# Display.net
KiCad netlist of a schematic drawn in EAGLE
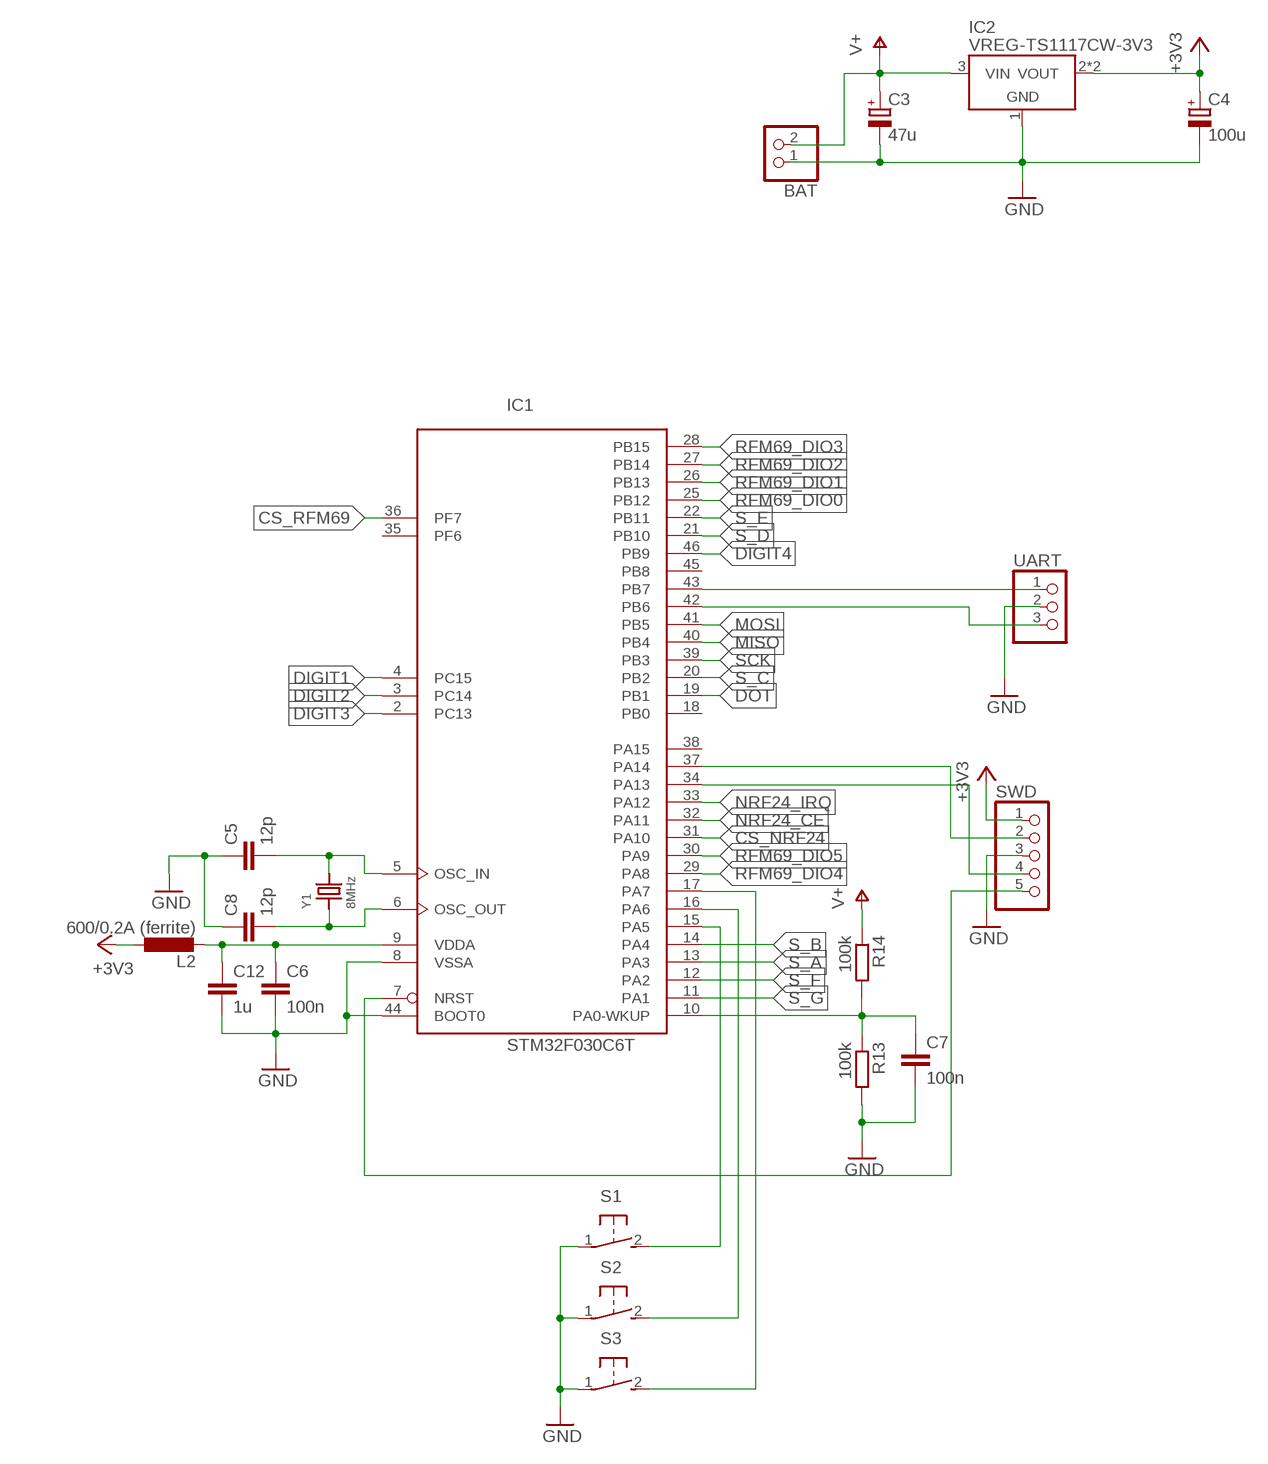
[diagram p0: schematic, sheet 1, part 1 of 2]
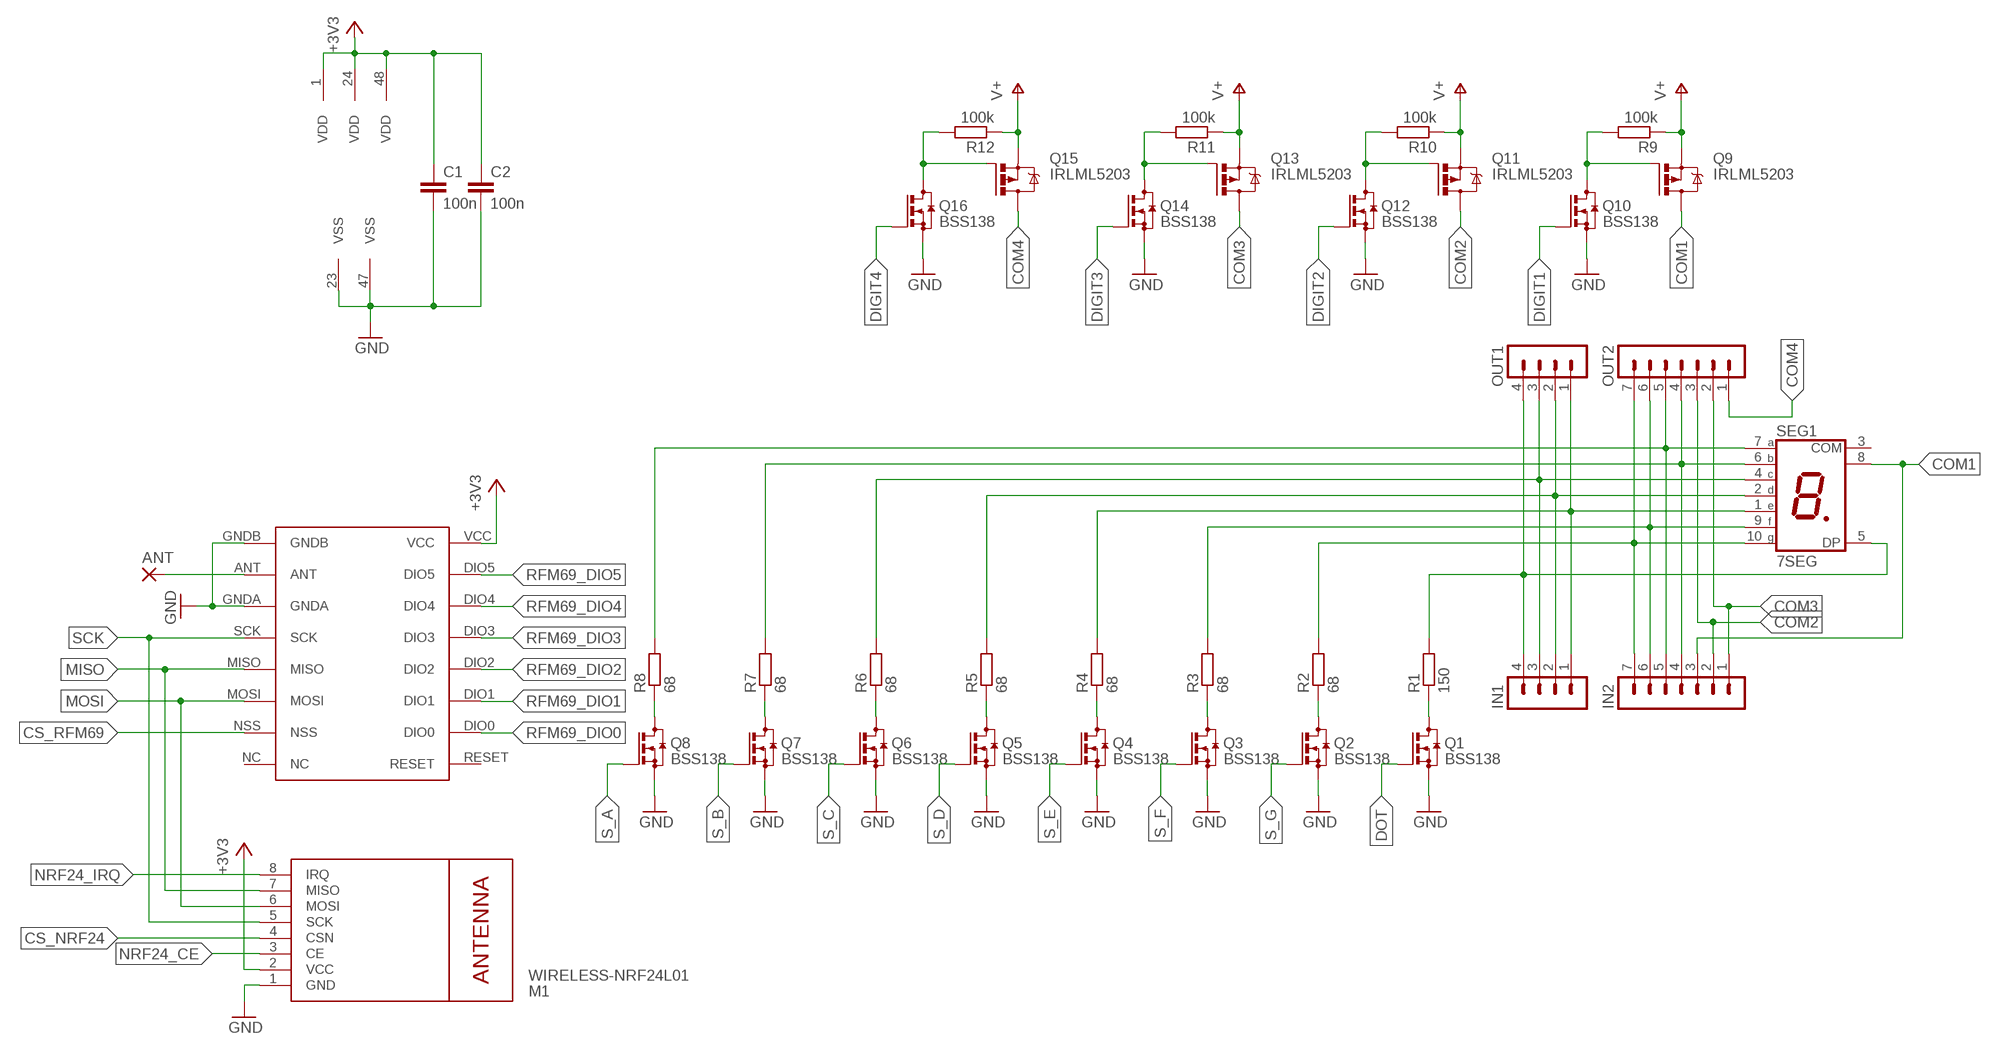
[diagram p1: schematic, sheet 1, part 2 of 2]

(export (version "E")
  (design (tool "Eeschema 10.0.6"))
  (components
    (comp (ref "ANT")
      (value "1,6/0,8")
      (footprint "eagle-import:1,6_0,8")
      (libsource (lib "eagle-import") (part "1,6/0,8"))
    )
    (comp (ref "BAT")
      (value "PINHD-1X2/90")
      (footprint "eagle-import:1X02_90")
      (libsource (lib "eagle-import") (part "PINHD-1X2/90"))
    )
    (comp (ref "C1")
      (value "100n")
      (footprint "eagle-import:C0603K")
      (libsource (lib "eagle-import") (part "C-EUC0603K"))
    )
    (comp (ref "C2")
      (value "100n")
      (footprint "eagle-import:C0603K")
      (libsource (lib "eagle-import") (part "C-EUC0603K"))
    )
    (comp (ref "C3")
      (value "47u")
      (footprint "eagle-import:E2,5-6")
      (libsource (lib "eagle-import") (part "CPOL-EUE2.5-6"))
    )
    (comp (ref "C4")
      (value "100u")
      (footprint "eagle-import:E2,5-6")
      (libsource (lib "eagle-import") (part "CPOL-EUE2.5-6"))
    )
    (comp (ref "C5")
      (value "12p")
      (footprint "eagle-import:C0603")
      (libsource (lib "eagle-import") (part "C-EUC0603"))
    )
    (comp (ref "C6")
      (value "100n")
      (footprint "eagle-import:C0603")
      (libsource (lib "eagle-import") (part "C-EUC0603"))
    )
    (comp (ref "C7")
      (value "100n")
      (footprint "eagle-import:C0603")
      (libsource (lib "eagle-import") (part "C-EUC0603"))
    )
    (comp (ref "C8")
      (value "12p")
      (footprint "eagle-import:C0603")
      (libsource (lib "eagle-import") (part "C-EUC0603"))
    )
    (comp (ref "C12")
      (value "1u")
      (footprint "eagle-import:C0603")
      (libsource (lib "eagle-import") (part "C-EUC0603"))
    )
    (comp (ref "IC1")
      (value "STM32F030C6T")
      (footprint "eagle-import:LQFP48")
      (libsource (lib "eagle-import") (part "STM32F030CT6"))
    )
    (comp (ref "IC2")
      (value "VREG-TS1117CW-3V3")
      (footprint "eagle-import:SOT223")
      (libsource (lib "eagle-import") (part "VREG-TS1117CW-3V3"))
    )
    (comp (ref "IN1")
      (value "MA04-1")
      (footprint "eagle-import:MA04-1")
      (libsource (lib "eagle-import") (part "MA04-1"))
    )
    (comp (ref "IN2")
      (value "MA07-1")
      (footprint "eagle-import:MA07-1")
      (libsource (lib "eagle-import") (part "MA07-1"))
    )
    (comp (ref "L2")
      (value "600/0.2A (ferrite)")
      (footprint "eagle-import:L2012C")
      (libsource (lib "eagle-import") (part "L-EUL2012C"))
    )
    (comp (ref "M1")
      (value "WIRELESS-NRF24L01")
      (footprint "eagle-import:WIRELESS-NRF24L01")
      (libsource (lib "eagle-import") (part "WIRELESS-NRF24L01"))
    )
    (comp (ref "OUT1")
      (value "MA04-1")
      (footprint "eagle-import:MA04-1")
      (libsource (lib "eagle-import") (part "MA04-1"))
    )
    (comp (ref "OUT2")
      (value "MA07-1")
      (footprint "eagle-import:MA07-1")
      (libsource (lib "eagle-import") (part "MA07-1"))
    )
    (comp (ref "Q1")
      (value "BSS138")
      (footprint "eagle-import:SOT23")
      (libsource (lib "eagle-import") (part "BSS123"))
    )
    (comp (ref "Q2")
      (value "BSS138")
      (footprint "eagle-import:SOT23")
      (libsource (lib "eagle-import") (part "BSS123"))
    )
    (comp (ref "Q3")
      (value "BSS138")
      (footprint "eagle-import:SOT23")
      (libsource (lib "eagle-import") (part "BSS123"))
    )
    (comp (ref "Q4")
      (value "BSS138")
      (footprint "eagle-import:SOT23")
      (libsource (lib "eagle-import") (part "BSS123"))
    )
    (comp (ref "Q5")
      (value "BSS138")
      (footprint "eagle-import:SOT23")
      (libsource (lib "eagle-import") (part "BSS123"))
    )
    (comp (ref "Q6")
      (value "BSS138")
      (footprint "eagle-import:SOT23")
      (libsource (lib "eagle-import") (part "BSS123"))
    )
    (comp (ref "Q7")
      (value "BSS138")
      (footprint "eagle-import:SOT23")
      (libsource (lib "eagle-import") (part "BSS123"))
    )
    (comp (ref "Q8")
      (value "BSS138")
      (footprint "eagle-import:SOT23")
      (libsource (lib "eagle-import") (part "BSS123"))
    )
    (comp (ref "Q9")
      (value "IRLML5203")
      (footprint "eagle-import:MICRO3")
      (libsource (lib "eagle-import") (part "IRLML5203"))
    )
    (comp (ref "Q10")
      (value "BSS138")
      (footprint "eagle-import:SOT23")
      (libsource (lib "eagle-import") (part "BSS123"))
    )
    (comp (ref "Q11")
      (value "IRLML5203")
      (footprint "eagle-import:MICRO3")
      (libsource (lib "eagle-import") (part "IRLML5203"))
    )
    (comp (ref "Q12")
      (value "BSS138")
      (footprint "eagle-import:SOT23")
      (libsource (lib "eagle-import") (part "BSS123"))
    )
    (comp (ref "Q13")
      (value "IRLML5203")
      (footprint "eagle-import:MICRO3")
      (libsource (lib "eagle-import") (part "IRLML5203"))
    )
    (comp (ref "Q14")
      (value "BSS138")
      (footprint "eagle-import:SOT23")
      (libsource (lib "eagle-import") (part "BSS123"))
    )
    (comp (ref "Q15")
      (value "IRLML5203")
      (footprint "eagle-import:MICRO3")
      (libsource (lib "eagle-import") (part "IRLML5203"))
    )
    (comp (ref "Q16")
      (value "BSS138")
      (footprint "eagle-import:SOT23")
      (libsource (lib "eagle-import") (part "BSS123"))
    )
    (comp (ref "R1")
      (value "150")
      (footprint "eagle-import:R1206")
      (libsource (lib "eagle-import") (part "R-EU_R1206"))
    )
    (comp (ref "R2")
      (value "68")
      (footprint "eagle-import:R1206")
      (libsource (lib "eagle-import") (part "R-EU_R1206"))
    )
    (comp (ref "R3")
      (value "68")
      (footprint "eagle-import:R1206")
      (libsource (lib "eagle-import") (part "R-EU_R1206"))
    )
    (comp (ref "R4")
      (value "68")
      (footprint "eagle-import:R1206")
      (libsource (lib "eagle-import") (part "R-EU_R1206"))
    )
    (comp (ref "R5")
      (value "68")
      (footprint "eagle-import:R1206")
      (libsource (lib "eagle-import") (part "R-EU_R1206"))
    )
    (comp (ref "R6")
      (value "68")
      (footprint "eagle-import:R1206")
      (libsource (lib "eagle-import") (part "R-EU_R1206"))
    )
    (comp (ref "R7")
      (value "68")
      (footprint "eagle-import:R1206")
      (libsource (lib "eagle-import") (part "R-EU_R1206"))
    )
    (comp (ref "R8")
      (value "68")
      (footprint "eagle-import:R1206")
      (libsource (lib "eagle-import") (part "R-EU_R1206"))
    )
    (comp (ref "R9")
      (value "100k")
      (footprint "eagle-import:R0603")
      (libsource (lib "eagle-import") (part "resistor_R-EU_R0603"))
    )
    (comp (ref "R10")
      (value "100k")
      (footprint "eagle-import:R0603")
      (libsource (lib "eagle-import") (part "resistor_R-EU_R0603"))
    )
    (comp (ref "R11")
      (value "100k")
      (footprint "eagle-import:R0603")
      (libsource (lib "eagle-import") (part "resistor_R-EU_R0603"))
    )
    (comp (ref "R12")
      (value "100k")
      (footprint "eagle-import:R0603")
      (libsource (lib "eagle-import") (part "resistor_R-EU_R0603"))
    )
    (comp (ref "R13")
      (value "100k")
      (footprint "eagle-import:R0603")
      (libsource (lib "eagle-import") (part "resistor_R-EU_R0603"))
    )
    (comp (ref "R14")
      (value "100k")
      (footprint "eagle-import:R0603")
      (libsource (lib "eagle-import") (part "resistor_R-EU_R0603"))
    )
    (comp (ref "S1")
      (value "31-XX")
      (footprint "eagle-import:B3F-31XX")
      (fields (field (name "MPN") "B3F-3100"))
      (libsource (lib "eagle-import") (part "31-XX"))
    )
    (comp (ref "S2")
      (value "31-XX")
      (footprint "eagle-import:B3F-31XX")
      (fields (field (name "MPN") "B3F-3100"))
      (libsource (lib "eagle-import") (part "31-XX"))
    )
    (comp (ref "S3")
      (value "31-XX")
      (footprint "eagle-import:B3F-31XX")
      (fields (field (name "MPN") "B3F-3100"))
      (libsource (lib "eagle-import") (part "31-XX"))
    )
    (comp (ref "SEG1")
      (value "7SEG")
      (footprint "eagle-import:7SEG_70_40")
      (libsource (lib "eagle-import") (part "7SEG"))
    )
    (comp (ref "SWD")
      (value "PINHD-1X5")
      (footprint "eagle-import:1X05")
      (libsource (lib "eagle-import") (part "PINHD-1X5"))
    )
    (comp (ref "U$1")
      (value "RFM69HW")
      (footprint "eagle-import:RFM")
      (libsource (lib "eagle-import") (part "RFM69HW"))
    )
    (comp (ref "UART")
      (value "PINHD-1X3")
      (footprint "eagle-import:1X03")
      (libsource (lib "eagle-import") (part "PINHD-1X3"))
    )
    (comp (ref "Y1")
      (value "8MHz")
      (footprint "eagle-import:3.2X2.5MM")
      (libsource (lib "eagle-import") (part "CRYSTAL.3.2X2.5MM"))
    )
  )
  (nets
    (net (code "1") (name "+3V3") (class "Default")
      (node (ref "C1") (pin "1") (pinfunction "1_1") (pintype "passive"))
      (node (ref "C2") (pin "1") (pinfunction "1_1") (pintype "passive"))
      (node (ref "C4") (pin "+") (pinfunction "+_+") (pintype "passive"))
      (node (ref "IC1") (pin "1") (pinfunction "VDD_1") (pintype "power_in"))
      (node (ref "IC1") (pin "24") (pinfunction "VDD_24") (pintype "power_in"))
      (node (ref "IC1") (pin "48") (pinfunction "VDD_48") (pintype "power_in"))
      (node (ref "IC2") (pin "2") (pinfunction "VOUT_2") (pintype "power_in"))
      (node (ref "IC2") (pin "4") (pinfunction "VOUT_4") (pintype "power_in"))
      (node (ref "L2") (pin "1") (pinfunction "1_1") (pintype "passive"))
      (node (ref "M1") (pin "2") (pinfunction "VCC_2") (pintype "power_in"))
      (node (ref "SWD") (pin "1") (pinfunction "1_1") (pintype "passive"))
      (node (ref "U$1") (pin "VCC") (pinfunction "VCC_VCC") (pintype "bidirectional"))
    )
    (net (code "2") (name "COM1") (class "Default")
      (node (ref "IN2") (pin "3") (pinfunction "3_3") (pintype "passive"))
      (node (ref "Q9") (pin "3") (pinfunction "D_3") (pintype "passive"))
      (node (ref "SEG1") (pin "8") (pinfunction "COM_8") (pintype "passive"))
    )
    (net (code "3") (name "COM2") (class "Default")
      (node (ref "IN2") (pin "2") (pinfunction "2_2") (pintype "passive"))
      (node (ref "OUT2") (pin "3") (pinfunction "3_3") (pintype "passive"))
      (node (ref "Q11") (pin "3") (pinfunction "D_3") (pintype "passive"))
    )
    (net (code "4") (name "COM3") (class "Default")
      (node (ref "IN2") (pin "1") (pinfunction "1_1") (pintype "passive"))
      (node (ref "OUT2") (pin "2") (pinfunction "2_2") (pintype "passive"))
      (node (ref "Q13") (pin "3") (pinfunction "D_3") (pintype "passive"))
    )
    (net (code "5") (name "COM4") (class "Default")
      (node (ref "OUT2") (pin "1") (pinfunction "1_1") (pintype "passive"))
      (node (ref "Q15") (pin "3") (pinfunction "D_3") (pintype "passive"))
    )
    (net (code "6") (name "CS_NRF24") (class "Default")
      (node (ref "IC1") (pin "31") (pinfunction "PA10_31") (pintype "bidirectional"))
      (node (ref "M1") (pin "4") (pinfunction "CSN_4") (pintype "bidirectional"))
    )
    (net (code "7") (name "CS_RFM69") (class "Default")
      (node (ref "IC1") (pin "36") (pinfunction "PF7_36") (pintype "bidirectional"))
      (node (ref "U$1") (pin "NSS") (pinfunction "NSS_NSS") (pintype "bidirectional"))
    )
    (net (code "8") (name "DIGIT1") (class "Default")
      (node (ref "IC1") (pin "4") (pinfunction "PC15_4") (pintype "bidirectional"))
      (node (ref "Q10") (pin "1") (pinfunction "G_1") (pintype "passive"))
    )
    (net (code "9") (name "DIGIT2") (class "Default")
      (node (ref "IC1") (pin "3") (pinfunction "PC14_3") (pintype "bidirectional"))
      (node (ref "Q12") (pin "1") (pinfunction "G_1") (pintype "passive"))
    )
    (net (code "10") (name "DIGIT3") (class "Default")
      (node (ref "IC1") (pin "2") (pinfunction "PC13_2") (pintype "bidirectional"))
      (node (ref "Q14") (pin "1") (pinfunction "G_1") (pintype "passive"))
    )
    (net (code "11") (name "DIGIT4") (class "Default")
      (node (ref "IC1") (pin "46") (pinfunction "PB9_46") (pintype "bidirectional"))
      (node (ref "Q16") (pin "1") (pinfunction "G_1") (pintype "passive"))
    )
    (net (code "12") (name "DOT") (class "Default")
      (node (ref "IC1") (pin "19") (pinfunction "PB1_19") (pintype "bidirectional"))
      (node (ref "Q1") (pin "1") (pinfunction "G_1") (pintype "passive"))
    )
    (net (code "13") (name "GND") (class "Default")
      (node (ref "BAT") (pin "1") (pinfunction "1_1") (pintype "passive"))
      (node (ref "C1") (pin "2") (pinfunction "2_2") (pintype "passive"))
      (node (ref "C12") (pin "2") (pinfunction "2_2") (pintype "passive"))
      (node (ref "C2") (pin "2") (pinfunction "2_2") (pintype "passive"))
      (node (ref "C3") (pin "-") (pinfunction "-_-") (pintype "passive"))
      (node (ref "C4") (pin "-") (pinfunction "-_-") (pintype "passive"))
      (node (ref "C5") (pin "1") (pinfunction "1_1") (pintype "passive"))
      (node (ref "C6") (pin "2") (pinfunction "2_2") (pintype "passive"))
      (node (ref "C7") (pin "2") (pinfunction "2_2") (pintype "passive"))
      (node (ref "C8") (pin "1") (pinfunction "1_1") (pintype "passive"))
      (node (ref "IC1") (pin "23") (pinfunction "VSS_23") (pintype "power_in"))
      (node (ref "IC1") (pin "44") (pinfunction "BOOT0_44") (pintype "input"))
      (node (ref "IC1") (pin "47") (pinfunction "VSS_47") (pintype "power_in"))
      (node (ref "IC1") (pin "8") (pinfunction "VSSA_8") (pintype "power_in"))
      (node (ref "IC2") (pin "1") (pinfunction "GND_1") (pintype "power_in"))
      (node (ref "M1") (pin "1") (pinfunction "GND_1") (pintype "power_in"))
      (node (ref "Q1") (pin "2") (pinfunction "S_2") (pintype "passive"))
      (node (ref "Q10") (pin "2") (pinfunction "S_2") (pintype "passive"))
      (node (ref "Q12") (pin "2") (pinfunction "S_2") (pintype "passive"))
      (node (ref "Q14") (pin "2") (pinfunction "S_2") (pintype "passive"))
      (node (ref "Q16") (pin "2") (pinfunction "S_2") (pintype "passive"))
      (node (ref "Q2") (pin "2") (pinfunction "S_2") (pintype "passive"))
      (node (ref "Q3") (pin "2") (pinfunction "S_2") (pintype "passive"))
      (node (ref "Q4") (pin "2") (pinfunction "S_2") (pintype "passive"))
      (node (ref "Q5") (pin "2") (pinfunction "S_2") (pintype "passive"))
      (node (ref "Q6") (pin "2") (pinfunction "S_2") (pintype "passive"))
      (node (ref "Q7") (pin "2") (pinfunction "S_2") (pintype "passive"))
      (node (ref "Q8") (pin "2") (pinfunction "S_2") (pintype "passive"))
      (node (ref "R13") (pin "2") (pinfunction "2_2") (pintype "passive"))
      (node (ref "S1") (pin "1") (pinfunction "P_1") (pintype "passive"))
      (node (ref "S2") (pin "1") (pinfunction "P_1") (pintype "passive"))
      (node (ref "S3") (pin "1") (pinfunction "P_1") (pintype "passive"))
      (node (ref "SWD") (pin "3") (pinfunction "3_3") (pintype "passive"))
      (node (ref "U$1") (pin "GNDA") (pinfunction "GNDA_GNDA") (pintype "bidirectional"))
      (node (ref "U$1") (pin "GNDB") (pinfunction "GNDB_GNDB") (pintype "bidirectional"))
      (node (ref "UART") (pin "2") (pinfunction "2_2") (pintype "passive"))
    )
    (net (code "14") (name "MISO") (class "Default")
      (node (ref "IC1") (pin "40") (pinfunction "PB4_40") (pintype "bidirectional"))
      (node (ref "M1") (pin "7") (pinfunction "MISO_7") (pintype "bidirectional"))
      (node (ref "U$1") (pin "MISO") (pinfunction "MISO_MISO") (pintype "bidirectional"))
    )
    (net (code "15") (name "MOSI") (class "Default")
      (node (ref "IC1") (pin "41") (pinfunction "PB5_41") (pintype "bidirectional"))
      (node (ref "M1") (pin "6") (pinfunction "MOSI_6") (pintype "bidirectional"))
      (node (ref "U$1") (pin "MOSI") (pinfunction "MOSI_MOSI") (pintype "bidirectional"))
    )
    (net (code "16") (name "NRF24_CE") (class "Default")
      (node (ref "IC1") (pin "32") (pinfunction "PA11_32") (pintype "bidirectional"))
      (node (ref "M1") (pin "3") (pinfunction "CE_3") (pintype "bidirectional"))
    )
    (net (code "17") (name "NRF24_IRQ") (class "Default")
      (node (ref "IC1") (pin "33") (pinfunction "PA12_33") (pintype "bidirectional"))
      (node (ref "M1") (pin "8") (pinfunction "IRQ_8") (pintype "bidirectional"))
    )
    (net (code "18") (name "Net-(ANT-P)") (class "Default")
      (node (ref "ANT") (pin "1") (pinfunction "P_1") (pintype "passive"))
      (node (ref "U$1") (pin "ANT") (pinfunction "ANT_ANT") (pintype "bidirectional"))
    )
    (net (code "19") (name "Net-(IC1A-NRST)") (class "Default")
      (node (ref "IC1") (pin "7") (pinfunction "NRST_7") (pintype "bidirectional"))
      (node (ref "SWD") (pin "5") (pinfunction "5_5") (pintype "passive"))
    )
    (net (code "20") (name "Net-(IC1A-OSC_IN)") (class "Default")
      (node (ref "C5") (pin "2") (pinfunction "2_2") (pintype "passive"))
      (node (ref "IC1") (pin "5") (pinfunction "OSC_IN_5") (pintype "bidirectional"))
      (node (ref "Y1") (pin "3") (pinfunction "2_3") (pintype "passive"))
    )
    (net (code "21") (name "Net-(IC1A-OSC_OUT)") (class "Default")
      (node (ref "C8") (pin "2") (pinfunction "2_2") (pintype "passive"))
      (node (ref "IC1") (pin "6") (pinfunction "OSC_OUT_6") (pintype "bidirectional"))
      (node (ref "Y1") (pin "1") (pinfunction "1_1") (pintype "passive"))
    )
    (net (code "22") (name "Net-(IC1A-PA0-WKUP)") (class "Default")
      (node (ref "C7") (pin "1") (pinfunction "1_1") (pintype "passive"))
      (node (ref "IC1") (pin "10") (pinfunction "PA0-WKUP_10") (pintype "bidirectional"))
      (node (ref "R13") (pin "1") (pinfunction "1_1") (pintype "passive"))
      (node (ref "R14") (pin "2") (pinfunction "2_2") (pintype "passive"))
    )
    (net (code "23") (name "Net-(IC1A-PA5)") (class "Default")
      (node (ref "IC1") (pin "15") (pinfunction "PA5_15") (pintype "bidirectional"))
      (node (ref "S1") (pin "2") (pinfunction "S_2") (pintype "passive"))
    )
    (net (code "24") (name "Net-(IC1A-PA6)") (class "Default")
      (node (ref "IC1") (pin "16") (pinfunction "PA6_16") (pintype "bidirectional"))
      (node (ref "S2") (pin "2") (pinfunction "S_2") (pintype "passive"))
    )
    (net (code "25") (name "Net-(IC1A-PA7)") (class "Default")
      (node (ref "IC1") (pin "17") (pinfunction "PA7_17") (pintype "bidirectional"))
      (node (ref "S3") (pin "2") (pinfunction "S_2") (pintype "passive"))
    )
    (net (code "26") (name "Net-(IC1A-PA13)") (class "Default")
      (node (ref "IC1") (pin "34") (pinfunction "PA13_34") (pintype "bidirectional"))
      (node (ref "SWD") (pin "4") (pinfunction "4_4") (pintype "passive"))
    )
    (net (code "27") (name "Net-(IC1A-PA14)") (class "Default")
      (node (ref "IC1") (pin "37") (pinfunction "PA14_37") (pintype "bidirectional"))
      (node (ref "SWD") (pin "2") (pinfunction "2_2") (pintype "passive"))
    )
    (net (code "28") (name "Net-(IC1A-PB6)") (class "Default")
      (node (ref "IC1") (pin "42") (pinfunction "PB6_42") (pintype "bidirectional"))
      (node (ref "UART") (pin "3") (pinfunction "3_3") (pintype "passive"))
    )
    (net (code "29") (name "Net-(IC1A-PB7)") (class "Default")
      (node (ref "IC1") (pin "43") (pinfunction "PB7_43") (pintype "bidirectional"))
      (node (ref "UART") (pin "1") (pinfunction "1_1") (pintype "passive"))
    )
    (net (code "30") (name "Net-(IC1A-VDDA)") (class "Default")
      (node (ref "C12") (pin "1") (pinfunction "1_1") (pintype "passive"))
      (node (ref "C6") (pin "1") (pinfunction "1_1") (pintype "passive"))
      (node (ref "IC1") (pin "9") (pinfunction "VDDA_9") (pintype "power_in"))
      (node (ref "L2") (pin "2") (pinfunction "2_2") (pintype "passive"))
    )
    (net (code "31") (name "Net-(Q1-D)") (class "Default")
      (node (ref "Q1") (pin "3") (pinfunction "D_3") (pintype "passive"))
      (node (ref "R1") (pin "1") (pinfunction "1_1") (pintype "passive"))
    )
    (net (code "32") (name "Net-(Q2-D)") (class "Default")
      (node (ref "Q2") (pin "3") (pinfunction "D_3") (pintype "passive"))
      (node (ref "R2") (pin "1") (pinfunction "1_1") (pintype "passive"))
    )
    (net (code "33") (name "Net-(Q3-D)") (class "Default")
      (node (ref "Q3") (pin "3") (pinfunction "D_3") (pintype "passive"))
      (node (ref "R3") (pin "1") (pinfunction "1_1") (pintype "passive"))
    )
    (net (code "34") (name "Net-(Q4-D)") (class "Default")
      (node (ref "Q4") (pin "3") (pinfunction "D_3") (pintype "passive"))
      (node (ref "R4") (pin "1") (pinfunction "1_1") (pintype "passive"))
    )
    (net (code "35") (name "Net-(Q5-D)") (class "Default")
      (node (ref "Q5") (pin "3") (pinfunction "D_3") (pintype "passive"))
      (node (ref "R5") (pin "1") (pinfunction "1_1") (pintype "passive"))
    )
    (net (code "36") (name "Net-(Q6-D)") (class "Default")
      (node (ref "Q6") (pin "3") (pinfunction "D_3") (pintype "passive"))
      (node (ref "R6") (pin "1") (pinfunction "1_1") (pintype "passive"))
    )
    (net (code "37") (name "Net-(Q7-D)") (class "Default")
      (node (ref "Q7") (pin "3") (pinfunction "D_3") (pintype "passive"))
      (node (ref "R7") (pin "1") (pinfunction "1_1") (pintype "passive"))
    )
    (net (code "38") (name "Net-(Q8-D)") (class "Default")
      (node (ref "Q8") (pin "3") (pinfunction "D_3") (pintype "passive"))
      (node (ref "R8") (pin "1") (pinfunction "1_1") (pintype "passive"))
    )
    (net (code "39") (name "Net-(Q10-D)") (class "Default")
      (node (ref "Q10") (pin "3") (pinfunction "D_3") (pintype "passive"))
      (node (ref "Q9") (pin "1") (pinfunction "G_1") (pintype "passive"))
      (node (ref "R9") (pin "2") (pinfunction "2_2") (pintype "passive"))
    )
    (net (code "40") (name "Net-(Q11-G)") (class "Default")
      (node (ref "Q11") (pin "1") (pinfunction "G_1") (pintype "passive"))
      (node (ref "Q12") (pin "3") (pinfunction "D_3") (pintype "passive"))
      (node (ref "R10") (pin "2") (pinfunction "2_2") (pintype "passive"))
    )
    (net (code "41") (name "Net-(Q13-G)") (class "Default")
      (node (ref "Q13") (pin "1") (pinfunction "G_1") (pintype "passive"))
      (node (ref "Q14") (pin "3") (pinfunction "D_3") (pintype "passive"))
      (node (ref "R11") (pin "2") (pinfunction "2_2") (pintype "passive"))
    )
    (net (code "42") (name "Net-(Q15-G)") (class "Default")
      (node (ref "Q15") (pin "1") (pinfunction "G_1") (pintype "passive"))
      (node (ref "Q16") (pin "3") (pinfunction "D_3") (pintype "passive"))
      (node (ref "R12") (pin "2") (pinfunction "2_2") (pintype "passive"))
    )
    (net (code "43") (name "Net-(SEG1-A)") (class "Default")
      (node (ref "IN2") (pin "5") (pinfunction "5_5") (pintype "passive"))
      (node (ref "OUT2") (pin "5") (pinfunction "5_5") (pintype "passive"))
      (node (ref "R8") (pin "2") (pinfunction "2_2") (pintype "passive"))
      (node (ref "SEG1") (pin "7") (pinfunction "A_7") (pintype "passive"))
    )
    (net (code "44") (name "Net-(SEG1-B)") (class "Default")
      (node (ref "IN2") (pin "4") (pinfunction "4_4") (pintype "passive"))
      (node (ref "OUT2") (pin "4") (pinfunction "4_4") (pintype "passive"))
      (node (ref "R7") (pin "2") (pinfunction "2_2") (pintype "passive"))
      (node (ref "SEG1") (pin "6") (pinfunction "B_6") (pintype "passive"))
    )
    (net (code "45") (name "Net-(SEG1-C)") (class "Default")
      (node (ref "IN1") (pin "3") (pinfunction "3_3") (pintype "passive"))
      (node (ref "OUT1") (pin "3") (pinfunction "3_3") (pintype "passive"))
      (node (ref "R6") (pin "2") (pinfunction "2_2") (pintype "passive"))
      (node (ref "SEG1") (pin "4") (pinfunction "C_4") (pintype "passive"))
    )
    (net (code "46") (name "Net-(SEG1-D)") (class "Default")
      (node (ref "IN1") (pin "2") (pinfunction "2_2") (pintype "passive"))
      (node (ref "OUT1") (pin "2") (pinfunction "2_2") (pintype "passive"))
      (node (ref "R5") (pin "2") (pinfunction "2_2") (pintype "passive"))
      (node (ref "SEG1") (pin "2") (pinfunction "D_2") (pintype "passive"))
    )
    (net (code "47") (name "Net-(SEG1-DP)") (class "Default")
      (node (ref "IN1") (pin "4") (pinfunction "4_4") (pintype "passive"))
      (node (ref "OUT1") (pin "4") (pinfunction "4_4") (pintype "passive"))
      (node (ref "R1") (pin "2") (pinfunction "2_2") (pintype "passive"))
      (node (ref "SEG1") (pin "5") (pinfunction "DP_5") (pintype "passive"))
    )
    (net (code "48") (name "Net-(SEG1-E)") (class "Default")
      (node (ref "IN1") (pin "1") (pinfunction "1_1") (pintype "passive"))
      (node (ref "OUT1") (pin "1") (pinfunction "1_1") (pintype "passive"))
      (node (ref "R4") (pin "2") (pinfunction "2_2") (pintype "passive"))
      (node (ref "SEG1") (pin "1") (pinfunction "E_1") (pintype "passive"))
    )
    (net (code "49") (name "Net-(SEG1-F)") (class "Default")
      (node (ref "IN2") (pin "6") (pinfunction "6_6") (pintype "passive"))
      (node (ref "OUT2") (pin "6") (pinfunction "6_6") (pintype "passive"))
      (node (ref "R3") (pin "2") (pinfunction "2_2") (pintype "passive"))
      (node (ref "SEG1") (pin "9") (pinfunction "F_9") (pintype "passive"))
    )
    (net (code "50") (name "Net-(SEG1-G)") (class "Default")
      (node (ref "IN2") (pin "7") (pinfunction "7_7") (pintype "passive"))
      (node (ref "OUT2") (pin "7") (pinfunction "7_7") (pintype "passive"))
      (node (ref "R2") (pin "2") (pinfunction "2_2") (pintype "passive"))
      (node (ref "SEG1") (pin "10") (pinfunction "G_10") (pintype "passive"))
    )
    (net (code "51") (name "RFM69_DIO0") (class "Default")
      (node (ref "IC1") (pin "25") (pinfunction "PB12_25") (pintype "bidirectional"))
      (node (ref "U$1") (pin "DIO0") (pinfunction "DIO0_DIO0") (pintype "bidirectional"))
    )
    (net (code "52") (name "RFM69_DIO1") (class "Default")
      (node (ref "IC1") (pin "26") (pinfunction "PB13_26") (pintype "bidirectional"))
      (node (ref "U$1") (pin "DIO1") (pinfunction "DIO1_DIO1") (pintype "bidirectional"))
    )
    (net (code "53") (name "RFM69_DIO2") (class "Default")
      (node (ref "IC1") (pin "27") (pinfunction "PB14_27") (pintype "bidirectional"))
      (node (ref "U$1") (pin "DIO2") (pinfunction "DIO2_DIO2") (pintype "bidirectional"))
    )
    (net (code "54") (name "RFM69_DIO3") (class "Default")
      (node (ref "IC1") (pin "28") (pinfunction "PB15_28") (pintype "bidirectional"))
      (node (ref "U$1") (pin "DIO3") (pinfunction "DIO3_DIO3") (pintype "bidirectional"))
    )
    (net (code "55") (name "RFM69_DIO4") (class "Default")
      (node (ref "IC1") (pin "29") (pinfunction "PA8_29") (pintype "bidirectional"))
      (node (ref "U$1") (pin "DIO4") (pinfunction "DIO4_DIO4") (pintype "bidirectional"))
    )
    (net (code "56") (name "RFM69_DIO5") (class "Default")
      (node (ref "IC1") (pin "30") (pinfunction "PA9_30") (pintype "bidirectional"))
      (node (ref "U$1") (pin "DIO5") (pinfunction "DIO5_DIO5") (pintype "bidirectional"))
    )
    (net (code "57") (name "SCK") (class "Default")
      (node (ref "IC1") (pin "39") (pinfunction "PB3_39") (pintype "bidirectional"))
      (node (ref "M1") (pin "5") (pinfunction "SCK_5") (pintype "bidirectional"))
      (node (ref "U$1") (pin "SCK") (pinfunction "SCK_SCK") (pintype "bidirectional"))
    )
    (net (code "58") (name "S_A") (class "Default")
      (node (ref "IC1") (pin "13") (pinfunction "PA3_13") (pintype "bidirectional"))
      (node (ref "Q8") (pin "1") (pinfunction "G_1") (pintype "passive"))
    )
    (net (code "59") (name "S_B") (class "Default")
      (node (ref "IC1") (pin "14") (pinfunction "PA4_14") (pintype "bidirectional"))
      (node (ref "Q7") (pin "1") (pinfunction "G_1") (pintype "passive"))
    )
    (net (code "60") (name "S_C") (class "Default")
      (node (ref "IC1") (pin "20") (pinfunction "PB2_20") (pintype "bidirectional"))
      (node (ref "Q6") (pin "1") (pinfunction "G_1") (pintype "passive"))
    )
    (net (code "61") (name "S_D") (class "Default")
      (node (ref "IC1") (pin "21") (pinfunction "PB10_21") (pintype "bidirectional"))
      (node (ref "Q5") (pin "1") (pinfunction "G_1") (pintype "passive"))
    )
    (net (code "62") (name "S_E") (class "Default")
      (node (ref "IC1") (pin "22") (pinfunction "PB11_22") (pintype "bidirectional"))
      (node (ref "Q4") (pin "1") (pinfunction "G_1") (pintype "passive"))
    )
    (net (code "63") (name "S_F") (class "Default")
      (node (ref "IC1") (pin "12") (pinfunction "PA2_12") (pintype "bidirectional"))
      (node (ref "Q3") (pin "1") (pinfunction "G_1") (pintype "passive"))
    )
    (net (code "64") (name "S_G") (class "Default")
      (node (ref "IC1") (pin "11") (pinfunction "PA1_11") (pintype "bidirectional"))
      (node (ref "Q2") (pin "1") (pinfunction "G_1") (pintype "passive"))
    )
    (net (code "65") (name "V+") (class "Default")
      (node (ref "BAT") (pin "2") (pinfunction "2_2") (pintype "passive"))
      (node (ref "C3") (pin "+") (pinfunction "+_+") (pintype "passive"))
      (node (ref "IC2") (pin "3") (pinfunction "VIN_3") (pintype "power_in"))
      (node (ref "Q11") (pin "2") (pinfunction "S_2") (pintype "passive"))
      (node (ref "Q13") (pin "2") (pinfunction "S_2") (pintype "passive"))
      (node (ref "Q15") (pin "2") (pinfunction "S_2") (pintype "passive"))
      (node (ref "Q9") (pin "2") (pinfunction "S_2") (pintype "passive"))
      (node (ref "R10") (pin "1") (pinfunction "1_1") (pintype "passive"))
      (node (ref "R11") (pin "1") (pinfunction "1_1") (pintype "passive"))
      (node (ref "R12") (pin "1") (pinfunction "1_1") (pintype "passive"))
      (node (ref "R14") (pin "1") (pinfunction "1_1") (pintype "passive"))
      (node (ref "R9") (pin "1") (pinfunction "1_1") (pintype "passive"))
    )
    (net (code "66") (name "unconnected-(IC1A-PA15-Pad38)") (class "Default")
      (node (ref "IC1") (pin "38") (pinfunction "PA15_38") (pintype "bidirectional"))
    )
    (net (code "67") (name "unconnected-(IC1A-PB0-Pad18)") (class "Default")
      (node (ref "IC1") (pin "18") (pinfunction "PB0_18") (pintype "bidirectional"))
    )
    (net (code "68") (name "unconnected-(IC1A-PB8-Pad45)") (class "Default")
      (node (ref "IC1") (pin "45") (pinfunction "PB8_45") (pintype "bidirectional"))
    )
    (net (code "69") (name "unconnected-(IC1A-PF6-Pad35)") (class "Default")
      (node (ref "IC1") (pin "35") (pinfunction "PF6_35") (pintype "bidirectional"))
    )
    (net (code "70") (name "unconnected-(SEG1-COM-Pad3)") (class "Default")
      (node (ref "SEG1") (pin "3") (pinfunction "COM_3") (pintype "passive"))
    )
    (net (code "71") (name "unconnected-(U$1-PadNC)") (class "Default")
      (node (ref "U$1") (pin "NC") (pinfunction "NC_NC") (pintype "bidirectional"))
    )
    (net (code "72") (name "unconnected-(U$1-PadRESET)") (class "Default")
      (node (ref "U$1") (pin "RESET") (pinfunction "RESET_RESET") (pintype "bidirectional"))
    )
  )
)
